# Syno_Ver1_1.net
KiCad netlist of a schematic drawn in EAGLE
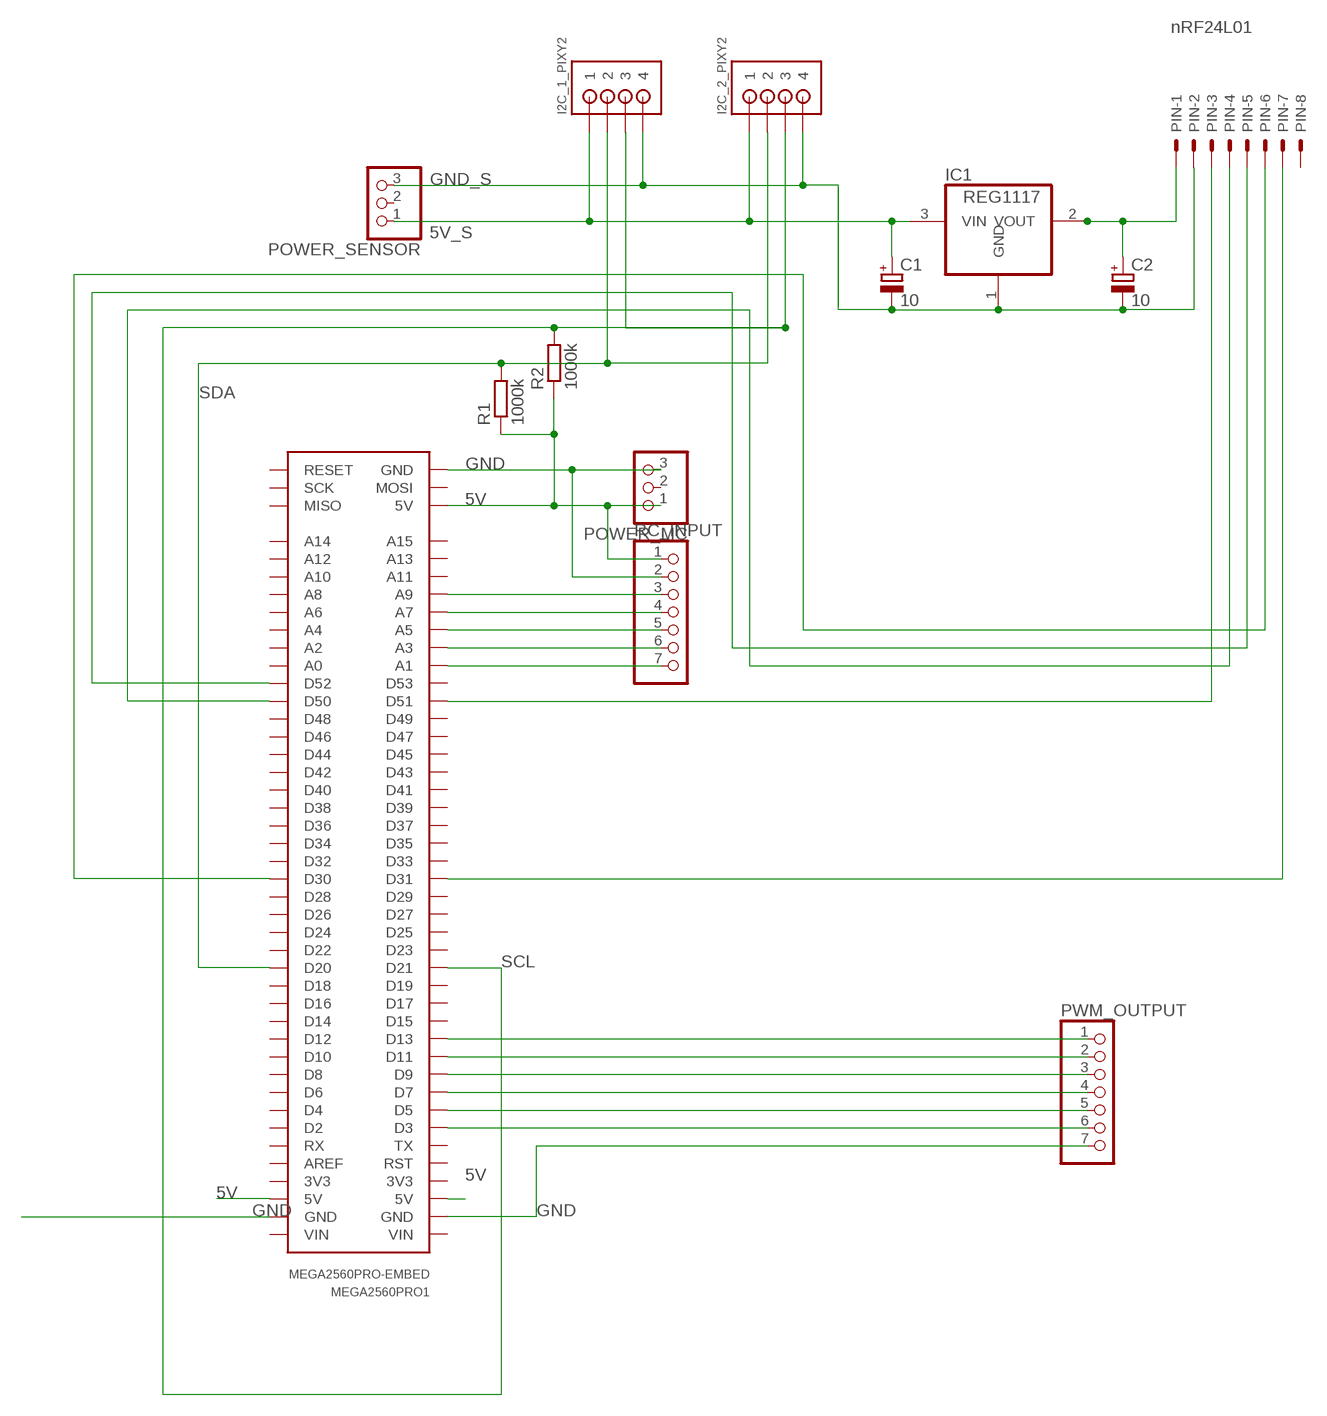
[diagram p0: schematic, sheet 1]

(export (version "E")
  (design (tool "Eeschema 10.0.6"))
  (components
    (comp (ref "C1")
      (value "10")
      (footprint "eagle-import:E1,8-4")
      (libsource (lib "eagle-import") (part "CPOL-EUE1.8-4"))
    )
    (comp (ref "C2")
      (value "10")
      (footprint "eagle-import:E1,8-4")
      (libsource (lib "eagle-import") (part "CPOL-EUE1.8-4"))
    )
    (comp (ref "I2C_1_PIXY2")
      (value "JST-PH_4-PIN_HEADER")
      (footprint "eagle-import:JST_B4B-PH_HEADER")
      (libsource (lib "eagle-import") (part "JST-PH_4-PIN_HEADER"))
    )
    (comp (ref "I2C_2_PIXY2")
      (value "JST-PH_4-PIN_HEADER")
      (footprint "eagle-import:JST_B4B-PH_HEADER")
      (libsource (lib "eagle-import") (part "JST-PH_4-PIN_HEADER"))
    )
    (comp (ref "IC1")
      (value "REG1117")
      (footprint "eagle-import:SOT223")
      (libsource (lib "eagle-import") (part "REG1117"))
    )
    (comp (ref "MEGA2560PRO1")
      (value "MEGA2560PRO-EMBED")
      (footprint "eagle-import:MEGA2560PRO-EMBED")
      (libsource (lib "eagle-import") (part "MEGA2560PRO-EMBED"))
    )
    (comp (ref "PIN")
      (value "nRF24L01")
      (footprint "eagle-import:JST-XH-08-PACKAGE-ROUND-PAD")
      (libsource (lib "eagle-import") (part "JST-XH-08-PIN-ROUND-PAD"))
    )
    (comp (ref "POWER_MC")
      (value "PINHD-1X3/90")
      (footprint "eagle-import:1X03_90")
      (libsource (lib "eagle-import") (part "PINHD-1X3/90"))
    )
    (comp (ref "POWER_SENSOR")
      (value "PINHD-1X3/90")
      (footprint "eagle-import:1X03_90")
      (libsource (lib "eagle-import") (part "PINHD-1X3/90"))
    )
    (comp (ref "PWM_OUTPUT")
      (value "PINHD-1X7/90")
      (footprint "eagle-import:1X07_90")
      (libsource (lib "eagle-import") (part "PINHD-1X7/90"))
    )
    (comp (ref "R1")
      (value "1000k")
      (footprint "eagle-import:0204_5")
      (libsource (lib "eagle-import") (part "R-EU_0204/5"))
    )
    (comp (ref "R2")
      (value "1000k")
      (footprint "eagle-import:0204_5")
      (libsource (lib "eagle-import") (part "R-EU_0204/5"))
    )
    (comp (ref "RC_INPUT")
      (value "PINHD-1X7/90")
      (footprint "eagle-import:1X07_90")
      (libsource (lib "eagle-import") (part "PINHD-1X7/90"))
    )
  )
  (nets
    (net (code "1") (name "/5V") (class "Default")
      (node (ref "MEGA2560PRO1") (pin "5V@1") (pinfunction "5V_5V@1") (pintype "bidirectional"))
      (node (ref "MEGA2560PRO1") (pin "5V@2") (pinfunction "5V_5V@2") (pintype "bidirectional"))
      (node (ref "MEGA2560PRO1") (pin "5V@3") (pinfunction "5V_5V@3") (pintype "bidirectional"))
      (node (ref "POWER_MC") (pin "1") (pinfunction "1_1") (pintype "passive"))
      (node (ref "R1") (pin "1") (pinfunction "1_1") (pintype "passive"))
      (node (ref "R2") (pin "1") (pinfunction "1_1") (pintype "passive"))
      (node (ref "RC_INPUT") (pin "1") (pinfunction "1_1") (pintype "passive"))
    )
    (net (code "2") (name "/5V_S") (class "Default")
      (node (ref "C1") (pin "+") (pinfunction "+_+") (pintype "passive"))
      (node (ref "I2C_1_PIXY2") (pin "P1") (pinfunction "1_P1") (pintype "bidirectional"))
      (node (ref "I2C_2_PIXY2") (pin "P1") (pinfunction "1_P1") (pintype "bidirectional"))
      (node (ref "IC1") (pin "3") (pinfunction "VIN_3") (pintype "input"))
      (node (ref "POWER_SENSOR") (pin "1") (pinfunction "1_1") (pintype "passive"))
    )
    (net (code "3") (name "/GND") (class "Default")
      (node (ref "MEGA2560PRO1") (pin "GND@1") (pinfunction "GND_GND@1") (pintype "bidirectional"))
      (node (ref "MEGA2560PRO1") (pin "GND@2") (pinfunction "GND_GND@2") (pintype "bidirectional"))
      (node (ref "MEGA2560PRO1") (pin "GND@3") (pinfunction "GND_GND@3") (pintype "bidirectional"))
      (node (ref "POWER_MC") (pin "3") (pinfunction "3_3") (pintype "passive"))
      (node (ref "PWM_OUTPUT") (pin "7") (pinfunction "7_7") (pintype "passive"))
      (node (ref "RC_INPUT") (pin "2") (pinfunction "2_2") (pintype "passive"))
    )
    (net (code "4") (name "/GND_S") (class "Default")
      (node (ref "C1") (pin "-") (pinfunction "-_-") (pintype "passive"))
      (node (ref "C2") (pin "-") (pinfunction "-_-") (pintype "passive"))
      (node (ref "I2C_1_PIXY2") (pin "P4") (pinfunction "4_P4") (pintype "bidirectional"))
      (node (ref "I2C_2_PIXY2") (pin "P4") (pinfunction "4_P4") (pintype "bidirectional"))
      (node (ref "IC1") (pin "1") (pinfunction "GND_1") (pintype "power_in"))
      (node (ref "PIN") (pin "2") (pinfunction "S_2") (pintype "passive"))
      (node (ref "POWER_SENSOR") (pin "3") (pinfunction "3_3") (pintype "passive"))
    )
    (net (code "5") (name "/SCL") (class "Default")
      (node (ref "I2C_1_PIXY2") (pin "P3") (pinfunction "3_P3") (pintype "bidirectional"))
      (node (ref "I2C_2_PIXY2") (pin "P3") (pinfunction "3_P3") (pintype "bidirectional"))
      (node (ref "MEGA2560PRO1") (pin "D21") (pinfunction "D21_D21") (pintype "bidirectional"))
      (node (ref "R2") (pin "2") (pinfunction "2_2") (pintype "passive"))
    )
    (net (code "6") (name "/SDA") (class "Default")
      (node (ref "I2C_1_PIXY2") (pin "P2") (pinfunction "2_P2") (pintype "bidirectional"))
      (node (ref "I2C_2_PIXY2") (pin "P2") (pinfunction "2_P2") (pintype "bidirectional"))
      (node (ref "MEGA2560PRO1") (pin "D20") (pinfunction "D20_D20") (pintype "bidirectional"))
      (node (ref "R1") (pin "2") (pinfunction "2_2") (pintype "passive"))
    )
    (net (code "7") (name "Net-(IC1-VOUT)") (class "Default")
      (node (ref "C2") (pin "+") (pinfunction "+_+") (pintype "passive"))
      (node (ref "IC1") (pin "2") (pinfunction "VOUT_2") (pintype "output"))
      (node (ref "PIN") (pin "1") (pinfunction "S_1") (pintype "passive"))
    )
    (net (code "8") (name "Net-(MEGA2560PRO1-PadA1)") (class "Default")
      (node (ref "MEGA2560PRO1") (pin "A1") (pinfunction "A1_A1") (pintype "bidirectional"))
      (node (ref "RC_INPUT") (pin "7") (pinfunction "7_7") (pintype "passive"))
    )
    (net (code "9") (name "Net-(MEGA2560PRO1-PadA3)") (class "Default")
      (node (ref "MEGA2560PRO1") (pin "A3") (pinfunction "A3_A3") (pintype "bidirectional"))
      (node (ref "RC_INPUT") (pin "6") (pinfunction "6_6") (pintype "passive"))
    )
    (net (code "10") (name "Net-(MEGA2560PRO1-PadA5)") (class "Default")
      (node (ref "MEGA2560PRO1") (pin "A5") (pinfunction "A5_A5") (pintype "bidirectional"))
      (node (ref "RC_INPUT") (pin "5") (pinfunction "5_5") (pintype "passive"))
    )
    (net (code "11") (name "Net-(MEGA2560PRO1-PadA7)") (class "Default")
      (node (ref "MEGA2560PRO1") (pin "A7") (pinfunction "A7_A7") (pintype "bidirectional"))
      (node (ref "RC_INPUT") (pin "4") (pinfunction "4_4") (pintype "passive"))
    )
    (net (code "12") (name "Net-(MEGA2560PRO1-PadA9)") (class "Default")
      (node (ref "MEGA2560PRO1") (pin "A9") (pinfunction "A9_A9") (pintype "bidirectional"))
      (node (ref "RC_INPUT") (pin "3") (pinfunction "3_3") (pintype "passive"))
    )
    (net (code "13") (name "Net-(MEGA2560PRO1-PadD3)") (class "Default")
      (node (ref "MEGA2560PRO1") (pin "D3") (pinfunction "D3_D3") (pintype "bidirectional"))
      (node (ref "PWM_OUTPUT") (pin "6") (pinfunction "6_6") (pintype "passive"))
    )
    (net (code "14") (name "Net-(MEGA2560PRO1-PadD5)") (class "Default")
      (node (ref "MEGA2560PRO1") (pin "D5") (pinfunction "D5_D5") (pintype "bidirectional"))
      (node (ref "PWM_OUTPUT") (pin "5") (pinfunction "5_5") (pintype "passive"))
    )
    (net (code "15") (name "Net-(MEGA2560PRO1-PadD7)") (class "Default")
      (node (ref "MEGA2560PRO1") (pin "D7") (pinfunction "D7_D7") (pintype "bidirectional"))
      (node (ref "PWM_OUTPUT") (pin "4") (pinfunction "4_4") (pintype "passive"))
    )
    (net (code "16") (name "Net-(MEGA2560PRO1-PadD9)") (class "Default")
      (node (ref "MEGA2560PRO1") (pin "D9") (pinfunction "D9_D9") (pintype "bidirectional"))
      (node (ref "PWM_OUTPUT") (pin "3") (pinfunction "3_3") (pintype "passive"))
    )
    (net (code "17") (name "Net-(MEGA2560PRO1-PadD11)") (class "Default")
      (node (ref "MEGA2560PRO1") (pin "D11") (pinfunction "D11_D11") (pintype "bidirectional"))
      (node (ref "PWM_OUTPUT") (pin "2") (pinfunction "2_2") (pintype "passive"))
    )
    (net (code "18") (name "Net-(MEGA2560PRO1-PadD13)") (class "Default")
      (node (ref "MEGA2560PRO1") (pin "D13") (pinfunction "D13_D13") (pintype "bidirectional"))
      (node (ref "PWM_OUTPUT") (pin "1") (pinfunction "1_1") (pintype "passive"))
    )
    (net (code "19") (name "Net-(PINC-S)") (class "Default")
      (node (ref "MEGA2560PRO1") (pin "D51") (pinfunction "D51_D51") (pintype "bidirectional"))
      (node (ref "PIN") (pin "3") (pinfunction "S_3") (pintype "passive"))
    )
    (net (code "20") (name "Net-(PIND-S)") (class "Default")
      (node (ref "MEGA2560PRO1") (pin "D50") (pinfunction "D50_D50") (pintype "bidirectional"))
      (node (ref "PIN") (pin "4") (pinfunction "S_4") (pintype "passive"))
    )
    (net (code "21") (name "Net-(PINE-S)") (class "Default")
      (node (ref "MEGA2560PRO1") (pin "D52") (pinfunction "D52_D52") (pintype "bidirectional"))
      (node (ref "PIN") (pin "5") (pinfunction "S_5") (pintype "passive"))
    )
    (net (code "22") (name "Net-(PINF-S)") (class "Default")
      (node (ref "MEGA2560PRO1") (pin "D30") (pinfunction "D30_D30") (pintype "bidirectional"))
      (node (ref "PIN") (pin "6") (pinfunction "S_6") (pintype "passive"))
    )
    (net (code "23") (name "Net-(PING-S)") (class "Default")
      (node (ref "MEGA2560PRO1") (pin "D31") (pinfunction "D31_D31") (pintype "bidirectional"))
      (node (ref "PIN") (pin "7") (pinfunction "S_7") (pintype "passive"))
    )
    (net (code "24") (name "unconnected-(MEGA2560PRO1-3V3-Pad3V3@1)") (class "Default")
      (node (ref "MEGA2560PRO1") (pin "3V3@1") (pinfunction "3V3_3V3@1") (pintype "bidirectional"))
    )
    (net (code "25") (name "unconnected-(MEGA2560PRO1-3V3-Pad3V3@2)") (class "Default")
      (node (ref "MEGA2560PRO1") (pin "3V3@2") (pinfunction "3V3_3V3@2") (pintype "bidirectional"))
    )
    (net (code "26") (name "unconnected-(MEGA2560PRO1-PadA0)") (class "Default")
      (node (ref "MEGA2560PRO1") (pin "A0") (pinfunction "A0_A0") (pintype "bidirectional"))
    )
    (net (code "27") (name "unconnected-(MEGA2560PRO1-PadA2)") (class "Default")
      (node (ref "MEGA2560PRO1") (pin "A2") (pinfunction "A2_A2") (pintype "bidirectional"))
    )
    (net (code "28") (name "unconnected-(MEGA2560PRO1-PadA4)") (class "Default")
      (node (ref "MEGA2560PRO1") (pin "A4") (pinfunction "A4_A4") (pintype "bidirectional"))
    )
    (net (code "29") (name "unconnected-(MEGA2560PRO1-PadA6)") (class "Default")
      (node (ref "MEGA2560PRO1") (pin "A6") (pinfunction "A6_A6") (pintype "bidirectional"))
    )
    (net (code "30") (name "unconnected-(MEGA2560PRO1-PadA8)") (class "Default")
      (node (ref "MEGA2560PRO1") (pin "A8") (pinfunction "A8_A8") (pintype "bidirectional"))
    )
    (net (code "31") (name "unconnected-(MEGA2560PRO1-PadA10)") (class "Default")
      (node (ref "MEGA2560PRO1") (pin "A10") (pinfunction "A10_A10") (pintype "bidirectional"))
    )
    (net (code "32") (name "unconnected-(MEGA2560PRO1-PadA11)") (class "Default")
      (node (ref "MEGA2560PRO1") (pin "A11") (pinfunction "A11_A11") (pintype "bidirectional"))
    )
    (net (code "33") (name "unconnected-(MEGA2560PRO1-PadA12)") (class "Default")
      (node (ref "MEGA2560PRO1") (pin "A12") (pinfunction "A12_A12") (pintype "bidirectional"))
    )
    (net (code "34") (name "unconnected-(MEGA2560PRO1-PadA13)") (class "Default")
      (node (ref "MEGA2560PRO1") (pin "A13") (pinfunction "A13_A13") (pintype "bidirectional"))
    )
    (net (code "35") (name "unconnected-(MEGA2560PRO1-PadA14)") (class "Default")
      (node (ref "MEGA2560PRO1") (pin "A14") (pinfunction "A14_A14") (pintype "bidirectional"))
    )
    (net (code "36") (name "unconnected-(MEGA2560PRO1-PadA15)") (class "Default")
      (node (ref "MEGA2560PRO1") (pin "A15") (pinfunction "A15_A15") (pintype "bidirectional"))
    )
    (net (code "37") (name "unconnected-(MEGA2560PRO1-PadAREF)") (class "Default")
      (node (ref "MEGA2560PRO1") (pin "AREF") (pinfunction "AREF_AREF") (pintype "bidirectional"))
    )
    (net (code "38") (name "unconnected-(MEGA2560PRO1-PadD2)") (class "Default")
      (node (ref "MEGA2560PRO1") (pin "D2") (pinfunction "D2_D2") (pintype "bidirectional"))
    )
    (net (code "39") (name "unconnected-(MEGA2560PRO1-PadD4)") (class "Default")
      (node (ref "MEGA2560PRO1") (pin "D4") (pinfunction "D4_D4") (pintype "bidirectional"))
    )
    (net (code "40") (name "unconnected-(MEGA2560PRO1-PadD6)") (class "Default")
      (node (ref "MEGA2560PRO1") (pin "D6") (pinfunction "D6_D6") (pintype "bidirectional"))
    )
    (net (code "41") (name "unconnected-(MEGA2560PRO1-PadD8)") (class "Default")
      (node (ref "MEGA2560PRO1") (pin "D8") (pinfunction "D8_D8") (pintype "bidirectional"))
    )
    (net (code "42") (name "unconnected-(MEGA2560PRO1-PadD10)") (class "Default")
      (node (ref "MEGA2560PRO1") (pin "D10") (pinfunction "D10_D10") (pintype "bidirectional"))
    )
    (net (code "43") (name "unconnected-(MEGA2560PRO1-PadD12)") (class "Default")
      (node (ref "MEGA2560PRO1") (pin "D12") (pinfunction "D12_D12") (pintype "bidirectional"))
    )
    (net (code "44") (name "unconnected-(MEGA2560PRO1-PadD14)") (class "Default")
      (node (ref "MEGA2560PRO1") (pin "D14") (pinfunction "D14_D14") (pintype "bidirectional"))
    )
    (net (code "45") (name "unconnected-(MEGA2560PRO1-PadD15)") (class "Default")
      (node (ref "MEGA2560PRO1") (pin "D15") (pinfunction "D15_D15") (pintype "bidirectional"))
    )
    (net (code "46") (name "unconnected-(MEGA2560PRO1-PadD16)") (class "Default")
      (node (ref "MEGA2560PRO1") (pin "D16") (pinfunction "D16_D16") (pintype "bidirectional"))
    )
    (net (code "47") (name "unconnected-(MEGA2560PRO1-PadD17)") (class "Default")
      (node (ref "MEGA2560PRO1") (pin "D17") (pinfunction "D17_D17") (pintype "bidirectional"))
    )
    (net (code "48") (name "unconnected-(MEGA2560PRO1-PadD18)") (class "Default")
      (node (ref "MEGA2560PRO1") (pin "D18") (pinfunction "D18_D18") (pintype "bidirectional"))
    )
    (net (code "49") (name "unconnected-(MEGA2560PRO1-PadD19)") (class "Default")
      (node (ref "MEGA2560PRO1") (pin "D19") (pinfunction "D19_D19") (pintype "bidirectional"))
    )
    (net (code "50") (name "unconnected-(MEGA2560PRO1-PadD22)") (class "Default")
      (node (ref "MEGA2560PRO1") (pin "D22") (pinfunction "D22_D22") (pintype "bidirectional"))
    )
    (net (code "51") (name "unconnected-(MEGA2560PRO1-PadD23)") (class "Default")
      (node (ref "MEGA2560PRO1") (pin "D23") (pinfunction "D23_D23") (pintype "bidirectional"))
    )
    (net (code "52") (name "unconnected-(MEGA2560PRO1-PadD24)") (class "Default")
      (node (ref "MEGA2560PRO1") (pin "D24") (pinfunction "D24_D24") (pintype "bidirectional"))
    )
    (net (code "53") (name "unconnected-(MEGA2560PRO1-PadD25)") (class "Default")
      (node (ref "MEGA2560PRO1") (pin "D25") (pinfunction "D25_D25") (pintype "bidirectional"))
    )
    (net (code "54") (name "unconnected-(MEGA2560PRO1-PadD26)") (class "Default")
      (node (ref "MEGA2560PRO1") (pin "D26") (pinfunction "D26_D26") (pintype "bidirectional"))
    )
    (net (code "55") (name "unconnected-(MEGA2560PRO1-PadD27)") (class "Default")
      (node (ref "MEGA2560PRO1") (pin "D27") (pinfunction "D27_D27") (pintype "bidirectional"))
    )
    (net (code "56") (name "unconnected-(MEGA2560PRO1-PadD28)") (class "Default")
      (node (ref "MEGA2560PRO1") (pin "D28") (pinfunction "D28_D28") (pintype "bidirectional"))
    )
    (net (code "57") (name "unconnected-(MEGA2560PRO1-PadD29)") (class "Default")
      (node (ref "MEGA2560PRO1") (pin "D29") (pinfunction "D29_D29") (pintype "bidirectional"))
    )
    (net (code "58") (name "unconnected-(MEGA2560PRO1-PadD32)") (class "Default")
      (node (ref "MEGA2560PRO1") (pin "D32") (pinfunction "D32_D32") (pintype "bidirectional"))
    )
    (net (code "59") (name "unconnected-(MEGA2560PRO1-PadD33)") (class "Default")
      (node (ref "MEGA2560PRO1") (pin "D33") (pinfunction "D33_D33") (pintype "bidirectional"))
    )
    (net (code "60") (name "unconnected-(MEGA2560PRO1-PadD34)") (class "Default")
      (node (ref "MEGA2560PRO1") (pin "D34") (pinfunction "D34_D34") (pintype "bidirectional"))
    )
    (net (code "61") (name "unconnected-(MEGA2560PRO1-PadD35)") (class "Default")
      (node (ref "MEGA2560PRO1") (pin "D35") (pinfunction "D35_D35") (pintype "bidirectional"))
    )
    (net (code "62") (name "unconnected-(MEGA2560PRO1-PadD36)") (class "Default")
      (node (ref "MEGA2560PRO1") (pin "D36") (pinfunction "D36_D36") (pintype "bidirectional"))
    )
    (net (code "63") (name "unconnected-(MEGA2560PRO1-PadD37)") (class "Default")
      (node (ref "MEGA2560PRO1") (pin "D37") (pinfunction "D37_D37") (pintype "bidirectional"))
    )
    (net (code "64") (name "unconnected-(MEGA2560PRO1-PadD38)") (class "Default")
      (node (ref "MEGA2560PRO1") (pin "D38") (pinfunction "D38_D38") (pintype "bidirectional"))
    )
    (net (code "65") (name "unconnected-(MEGA2560PRO1-PadD39)") (class "Default")
      (node (ref "MEGA2560PRO1") (pin "D39") (pinfunction "D39_D39") (pintype "bidirectional"))
    )
    (net (code "66") (name "unconnected-(MEGA2560PRO1-PadD40)") (class "Default")
      (node (ref "MEGA2560PRO1") (pin "D40") (pinfunction "D40_D40") (pintype "bidirectional"))
    )
    (net (code "67") (name "unconnected-(MEGA2560PRO1-PadD41)") (class "Default")
      (node (ref "MEGA2560PRO1") (pin "D41") (pinfunction "D41_D41") (pintype "bidirectional"))
    )
    (net (code "68") (name "unconnected-(MEGA2560PRO1-PadD42)") (class "Default")
      (node (ref "MEGA2560PRO1") (pin "D42") (pinfunction "D42_D42") (pintype "bidirectional"))
    )
    (net (code "69") (name "unconnected-(MEGA2560PRO1-PadD43)") (class "Default")
      (node (ref "MEGA2560PRO1") (pin "D43") (pinfunction "D43_D43") (pintype "bidirectional"))
    )
    (net (code "70") (name "unconnected-(MEGA2560PRO1-PadD44)") (class "Default")
      (node (ref "MEGA2560PRO1") (pin "D44") (pinfunction "D44_D44") (pintype "bidirectional"))
    )
    (net (code "71") (name "unconnected-(MEGA2560PRO1-PadD45)") (class "Default")
      (node (ref "MEGA2560PRO1") (pin "D45") (pinfunction "D45_D45") (pintype "bidirectional"))
    )
    (net (code "72") (name "unconnected-(MEGA2560PRO1-PadD46)") (class "Default")
      (node (ref "MEGA2560PRO1") (pin "D46") (pinfunction "D46_D46") (pintype "bidirectional"))
    )
    (net (code "73") (name "unconnected-(MEGA2560PRO1-PadD47)") (class "Default")
      (node (ref "MEGA2560PRO1") (pin "D47") (pinfunction "D47_D47") (pintype "bidirectional"))
    )
    (net (code "74") (name "unconnected-(MEGA2560PRO1-PadD48)") (class "Default")
      (node (ref "MEGA2560PRO1") (pin "D48") (pinfunction "D48_D48") (pintype "bidirectional"))
    )
    (net (code "75") (name "unconnected-(MEGA2560PRO1-PadD49)") (class "Default")
      (node (ref "MEGA2560PRO1") (pin "D49") (pinfunction "D49_D49") (pintype "bidirectional"))
    )
    (net (code "76") (name "unconnected-(MEGA2560PRO1-PadD53)") (class "Default")
      (node (ref "MEGA2560PRO1") (pin "D53") (pinfunction "D53_D53") (pintype "bidirectional"))
    )
    (net (code "77") (name "unconnected-(MEGA2560PRO1-PadMISO)") (class "Default")
      (node (ref "MEGA2560PRO1") (pin "MISO") (pinfunction "MISO_MISO") (pintype "bidirectional"))
    )
    (net (code "78") (name "unconnected-(MEGA2560PRO1-PadMOSI)") (class "Default")
      (node (ref "MEGA2560PRO1") (pin "MOSI") (pinfunction "MOSI_MOSI") (pintype "bidirectional"))
    )
    (net (code "79") (name "unconnected-(MEGA2560PRO1-PadRESET)") (class "Default")
      (node (ref "MEGA2560PRO1") (pin "RESET") (pinfunction "RESET_RESET") (pintype "bidirectional"))
    )
    (net (code "80") (name "unconnected-(MEGA2560PRO1-PadRST)") (class "Default")
      (node (ref "MEGA2560PRO1") (pin "RST") (pinfunction "RST_RST") (pintype "bidirectional"))
    )
    (net (code "81") (name "unconnected-(MEGA2560PRO1-PadRX)") (class "Default")
      (node (ref "MEGA2560PRO1") (pin "RX") (pinfunction "RX_RX") (pintype "bidirectional"))
    )
    (net (code "82") (name "unconnected-(MEGA2560PRO1-PadSCK)") (class "Default")
      (node (ref "MEGA2560PRO1") (pin "SCK") (pinfunction "SCK_SCK") (pintype "bidirectional"))
    )
    (net (code "83") (name "unconnected-(MEGA2560PRO1-PadTX)") (class "Default")
      (node (ref "MEGA2560PRO1") (pin "TX") (pinfunction "TX_TX") (pintype "bidirectional"))
    )
    (net (code "84") (name "unconnected-(MEGA2560PRO1-VIN-PadVIN@1)") (class "Default")
      (node (ref "MEGA2560PRO1") (pin "VIN@1") (pinfunction "VIN_VIN@1") (pintype "bidirectional"))
    )
    (net (code "85") (name "unconnected-(MEGA2560PRO1-VIN-PadVIN@2)") (class "Default")
      (node (ref "MEGA2560PRO1") (pin "VIN@2") (pinfunction "VIN_VIN@2") (pintype "bidirectional"))
    )
    (net (code "86") (name "unconnected-(PINH-S-Pad8)") (class "Default")
      (node (ref "PIN") (pin "8") (pinfunction "S_8") (pintype "passive"))
    )
    (net (code "87") (name "unconnected-(POWER_MC-Pad2)") (class "Default")
      (node (ref "POWER_MC") (pin "2") (pinfunction "2_2") (pintype "passive"))
    )
    (net (code "88") (name "unconnected-(POWER_SENSOR-Pad2)") (class "Default")
      (node (ref "POWER_SENSOR") (pin "2") (pinfunction "2_2") (pintype "passive"))
    )
  )
)
